# Main.net
KiCad netlist of a schematic drawn in Altium Designer
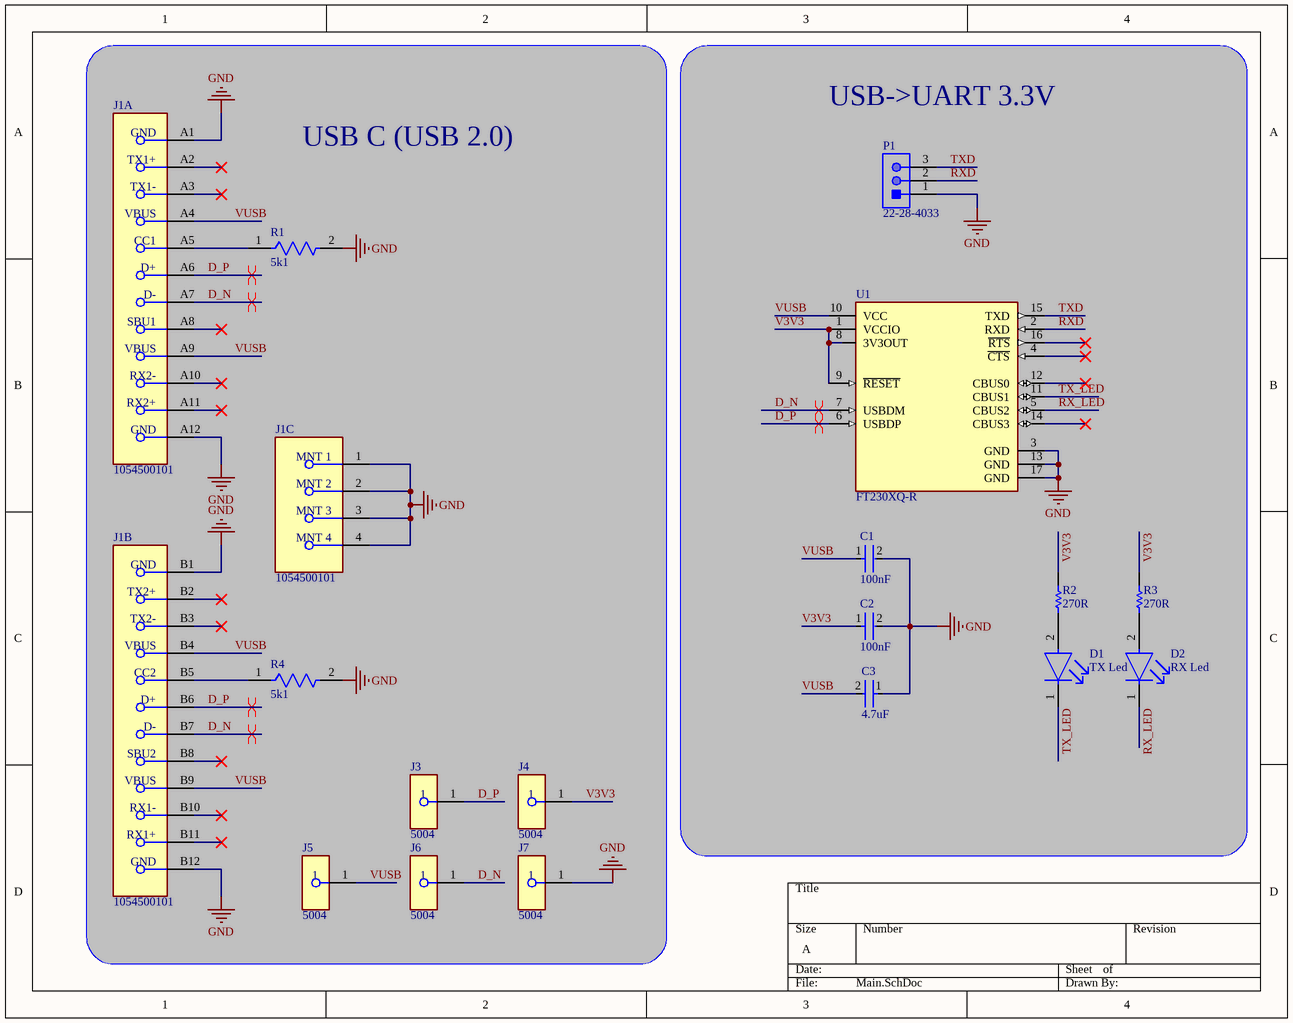
[diagram p0: Main.SchDoc]

(export (version "E")
  (design (tool "Eeschema 10.0.6"))
  (components
    (comp (ref "C1")
      (value "100nF")
      (footprint "FP-CGA3E-0_3-0_1-IPC_A")
      (description "Cap Ceramic 100nF 50V X7R 10% Pad SMD 0603 +125°C Automotive T/R")
      (fields (field (name "TOLERANCE") "10%") (field (name "VOLTAGE") "50V"))
      (libsource (lib "Altium Content Vault") (part "b4654b650e69147ec39a6b967a45e02"))
    )
    (comp (ref "C2")
      (value "100nF")
      (footprint "FP-CGA3E-0_3-0_1-IPC_A")
      (description "Cap Ceramic 100nF 50V X7R 10% Pad SMD 0603 +125°C Automotive T/R")
      (fields (field (name "TOLERANCE") "10%") (field (name "VOLTAGE") "50V"))
      (libsource (lib "Altium Content Vault") (part "b4654b650e69147ec39a6b967a45e02"))
    )
    (comp (ref "C3")
      (value "4.7uF")
      (footprint "FP-GRM188-0_2-IPC_C")
      (description "Chip Multilayer Ceramic Capacitors for General Purpose, 0603, 4.7uF, X5R, 15%, 10%, 35V")
      (fields (field (name "VOLTAGE") "35V") (field (name "TOLERANCE") "10%"))
      (libsource (lib "Altium Content Vault") (part "11868f565c42a9108669ba33697ecf6"))
    )
    (comp (ref "D1")
      (value "TX Led")
      (footprint "FP-LTST-C190GKT-MFG")
      (description "LED GREEN CLEAR CHIP SMD")
      (fields (field (name "VOLTAGE") "2V"))
      (libsource (lib "Altium Content Vault") (part "8706943c75ba83719d021d2fdc84c58"))
    )
    (comp (ref "D2")
      (value "RX Led")
      (footprint "FP-LTST-C190GKT-MFG")
      (description "LED GREEN CLEAR CHIP SMD")
      (fields (field (name "VOLTAGE") "2V"))
      (libsource (lib "Altium Content Vault") (part "8706943c75ba83719d021d2fdc84c58"))
    )
    (comp (ref "J1")
      (value "1054500101")
      (footprint "FP-1054500101-MFG")
      (description "USB Shielded I/O Receptacle; Type C; Right Angle; Surface Mount; Gold over Nickel")
      (fields (field (name "MANUFACTURER") "Molex"))
      (libsource (lib "Altium Content Vault") (part "9808b19ecaf079fb99eed69f0495cd0"))
    )
    (comp (ref "J3")
      (value "5004")
      (footprint "FP-5004-MFG")
      (description "PC TEST POINT MINIATURE YELLOW")
      (fields
        (field (name "MANUFACTURER") "Keystone")
        (field (name "OCTOPART") "https://octopart.com/5004-keystone-28591")
      )
      (libsource (lib "Altium Content Vault") (part "98815daf2f2c152b0c43f5ab9800df6"))
    )
    (comp (ref "J4")
      (value "5004")
      (footprint "FP-5004-MFG")
      (description "PC TEST POINT MINIATURE YELLOW")
      (fields
        (field (name "MANUFACTURER") "Keystone")
        (field (name "OCTOPART") "https://octopart.com/5004-keystone-28591")
      )
      (libsource (lib "Altium Content Vault") (part "98815daf2f2c152b0c43f5ab9800df6"))
    )
    (comp (ref "J5")
      (value "5004")
      (footprint "FP-5004-MFG")
      (description "PC TEST POINT MINIATURE YELLOW")
      (fields
        (field (name "MANUFACTURER") "Keystone")
        (field (name "OCTOPART") "https://octopart.com/5004-keystone-28591")
      )
      (libsource (lib "Altium Content Vault") (part "98815daf2f2c152b0c43f5ab9800df6"))
    )
    (comp (ref "J6")
      (value "5004")
      (footprint "FP-5004-MFG")
      (description "PC TEST POINT MINIATURE YELLOW")
      (fields
        (field (name "MANUFACTURER") "Keystone")
        (field (name "OCTOPART") "https://octopart.com/5004-keystone-28591")
      )
      (libsource (lib "Altium Content Vault") (part "98815daf2f2c152b0c43f5ab9800df6"))
    )
    (comp (ref "J7")
      (value "5004")
      (footprint "FP-5004-MFG")
      (description "PC TEST POINT MINIATURE YELLOW")
      (fields
        (field (name "MANUFACTURER") "Keystone")
        (field (name "OCTOPART") "https://octopart.com/5004-keystone-28591")
      )
      (libsource (lib "Altium Content Vault") (part "98815daf2f2c152b0c43f5ab9800df6"))
    )
    (comp (ref "P1")
      (value "22-28-4033")
      (footprint "MOLX-22-28-4033_V")
      (description "Male Header, Pitch 2.54 mm, 1 x 3 Position, Height 8.38 mm, Tail Length 3.18 mm, RoHS, Bulk")
      (fields (field (name "MANUFACTURER") "Molex"))
      (libsource (lib "Altium Content Vault") (part "CN-1P-M-R3"))
    )
    (comp (ref "R1")
      (value "5k1")
      (footprint "FP-CRCW0603-e3-IPC_C")
      (description "RES Thick Film, 5.1kΩ, 1%, 0.1W, 100ppm/°C, 0603")
      (fields (field (name "TOLERANCE") "1%"))
      (libsource (lib "Altium Content Vault") (part "1029c3af85768c4190bb7ad29bc67b5"))
    )
    (comp (ref "R2")
      (value "270R")
      (footprint "RESC1608X55X30LL15T15")
      (fields (field (name "MANUFACTURER") "Panasonic") (field (name "PART NUMBER") "ERJ3EKF2700V"))
      (libsource (lib "Altium Content Vault") (part "RES"))
    )
    (comp (ref "R3")
      (value "270R")
      (footprint "RESC1608X55X30LL15T15")
      (fields (field (name "MANUFACTURER") "Panasonic") (field (name "PART NUMBER") "ERJ3EKF2700V"))
      (libsource (lib "Altium Content Vault") (part "RES"))
    )
    (comp (ref "R4")
      (value "5k1")
      (footprint "FP-CRCW0603-e3-IPC_C")
      (description "RES Thick Film, 5.1kΩ, 1%, 0.1W, 100ppm/°C, 0603")
      (fields (field (name "TOLERANCE") "1%"))
      (libsource (lib "Altium Content Vault") (part "1029c3af85768c4190bb7ad29bc67b5"))
    )
    (comp (ref "U1")
      (value "FT230XQ-R")
      (footprint "FP-QFN-16-MFG")
      (description "IC USB SERIAL BASIC UART 16QFN")
      (libsource (lib "Altium Content Vault") (part "29d2eb9587eff32afae5da052de4085"))
    )
  )
  (nets
    (net (code "1") (name "/D_N") (class "Default")
      (node (ref "J1") (pin "A7") (pinfunction "D-_A7") (pintype "passive"))
      (node (ref "J1") (pin "B7") (pinfunction "D-_B7") (pintype "passive"))
      (node (ref "J6") (pin "1") (pinfunction "1_1") (pintype "passive"))
      (node (ref "U1") (pin "7") (pinfunction "USBDM_7") (pintype "input"))
    )
    (net (code "2") (name "/D_P") (class "Default")
      (node (ref "J1") (pin "A6") (pinfunction "D+_A6") (pintype "passive"))
      (node (ref "J1") (pin "B6") (pinfunction "D+_B6") (pintype "passive"))
      (node (ref "J3") (pin "1") (pinfunction "1_1") (pintype "passive"))
      (node (ref "U1") (pin "6") (pinfunction "USBDP_6") (pintype "input"))
    )
    (net (code "3") (name "/RXD") (class "Default")
      (node (ref "P1") (pin "2") (pinfunction "2_2") (pintype "passive"))
      (node (ref "U1") (pin "2") (pinfunction "RXD_2") (pintype "input"))
    )
    (net (code "4") (name "/RX_LED") (class "Default")
      (node (ref "D2") (pin "1") (pinfunction "C_1") (pintype "passive"))
      (node (ref "U1") (pin "5") (pinfunction "CBUS2_5") (pintype "bidirectional"))
    )
    (net (code "5") (name "/TXD") (class "Default")
      (node (ref "P1") (pin "3") (pinfunction "3_3") (pintype "passive"))
      (node (ref "U1") (pin "15") (pinfunction "TXD_15") (pintype "output"))
    )
    (net (code "6") (name "/TX_LED") (class "Default")
      (node (ref "D1") (pin "1") (pinfunction "C_1") (pintype "passive"))
      (node (ref "U1") (pin "11") (pinfunction "CBUS1_11") (pintype "bidirectional"))
    )
    (net (code "7") (name "/V3V3") (class "Default")
      (node (ref "C2") (pin "1") (pinfunction "1_1") (pintype "passive"))
      (node (ref "J4") (pin "1") (pinfunction "1_1") (pintype "passive"))
      (node (ref "R2") (pin "2") (pinfunction "2_2") (pintype "passive"))
      (node (ref "R3") (pin "2") (pinfunction "2_2") (pintype "passive"))
      (node (ref "U1") (pin "1") (pinfunction "VCCIO_1") (pintype "power_in"))
      (node (ref "U1") (pin "8") (pinfunction "3V3OUT_8") (pintype "power_in"))
      (node (ref "U1") (pin "9") (pinfunction "~{RESET}_9") (pintype "input"))
    )
    (net (code "8") (name "/VUSB") (class "Default")
      (node (ref "C1") (pin "1") (pinfunction "1_1") (pintype "passive"))
      (node (ref "C3") (pin "2") (pinfunction "2_2") (pintype "passive"))
      (node (ref "J1") (pin "A4") (pinfunction "VBUS_A4") (pintype "passive"))
      (node (ref "J1") (pin "A9") (pinfunction "VBUS_A9") (pintype "passive"))
      (node (ref "J1") (pin "B4") (pinfunction "VBUS_B4") (pintype "passive"))
      (node (ref "J1") (pin "B9") (pinfunction "VBUS_B9") (pintype "passive"))
      (node (ref "J5") (pin "1") (pinfunction "1_1") (pintype "passive"))
      (node (ref "U1") (pin "10") (pinfunction "VCC_10") (pintype "power_in"))
    )
    (net (code "9") (name "GND") (class "Default")
      (node (ref "C1") (pin "2") (pinfunction "2_2") (pintype "passive"))
      (node (ref "C2") (pin "2") (pinfunction "2_2") (pintype "passive"))
      (node (ref "C3") (pin "1") (pinfunction "1_1") (pintype "passive"))
      (node (ref "J1") (pin "1") (pinfunction "MNT_1_1") (pintype "passive"))
      (node (ref "J1") (pin "2") (pinfunction "MNT_2_2") (pintype "passive"))
      (node (ref "J1") (pin "3") (pinfunction "MNT_3_3") (pintype "passive"))
      (node (ref "J1") (pin "4") (pinfunction "MNT_4_4") (pintype "passive"))
      (node (ref "J1") (pin "A1") (pinfunction "GND_A1") (pintype "passive"))
      (node (ref "J1") (pin "A12") (pinfunction "GND_A12") (pintype "passive"))
      (node (ref "J1") (pin "B1") (pinfunction "GND_B1") (pintype "passive"))
      (node (ref "J1") (pin "B12") (pinfunction "GND_B12") (pintype "passive"))
      (node (ref "J7") (pin "1") (pinfunction "1_1") (pintype "passive"))
      (node (ref "P1") (pin "1") (pinfunction "1_1") (pintype "passive"))
      (node (ref "R1") (pin "2") (pinfunction "2_2") (pintype "passive"))
      (node (ref "R4") (pin "2") (pinfunction "2_2") (pintype "passive"))
      (node (ref "U1") (pin "13") (pinfunction "GND_13") (pintype "power_in"))
      (node (ref "U1") (pin "17") (pinfunction "GND_17") (pintype "power_in"))
      (node (ref "U1") (pin "3") (pinfunction "GND_3") (pintype "power_in"))
    )
    (net (code "10") (name "Net-(D1-A)") (class "Default")
      (node (ref "D1") (pin "2") (pinfunction "A_2") (pintype "passive"))
      (node (ref "R2") (pin "1") (pinfunction "1_1") (pintype "passive"))
    )
    (net (code "11") (name "Net-(D2-A)") (class "Default")
      (node (ref "D2") (pin "2") (pinfunction "A_2") (pintype "passive"))
      (node (ref "R3") (pin "1") (pinfunction "1_1") (pintype "passive"))
    )
    (net (code "12") (name "Net-(J1A-CC1)") (class "Default")
      (node (ref "J1") (pin "A5") (pinfunction "CC1_A5") (pintype "passive"))
      (node (ref "R1") (pin "1") (pinfunction "1_1") (pintype "passive"))
    )
    (net (code "13") (name "Net-(J1B-CC2)") (class "Default")
      (node (ref "J1") (pin "B5") (pinfunction "CC2_B5") (pintype "passive"))
      (node (ref "R4") (pin "1") (pinfunction "1_1") (pintype "passive"))
    )
    (net (code "14") (name "unconnected-(J1A-RX2+-PadA11)") (class "Default")
      (node (ref "J1") (pin "A11") (pinfunction "RX2+_A11") (pintype "passive+no_connect"))
    )
    (net (code "15") (name "unconnected-(J1A-RX2--PadA10)") (class "Default")
      (node (ref "J1") (pin "A10") (pinfunction "RX2-_A10") (pintype "passive+no_connect"))
    )
    (net (code "16") (name "unconnected-(J1A-SBU1-PadA8)") (class "Default")
      (node (ref "J1") (pin "A8") (pinfunction "SBU1_A8") (pintype "passive+no_connect"))
    )
    (net (code "17") (name "unconnected-(J1A-TX1+-PadA2)") (class "Default")
      (node (ref "J1") (pin "A2") (pinfunction "TX1+_A2") (pintype "passive+no_connect"))
    )
    (net (code "18") (name "unconnected-(J1A-TX1--PadA3)") (class "Default")
      (node (ref "J1") (pin "A3") (pinfunction "TX1-_A3") (pintype "passive+no_connect"))
    )
    (net (code "19") (name "unconnected-(J1B-RX1+-PadB11)") (class "Default")
      (node (ref "J1") (pin "B11") (pinfunction "RX1+_B11") (pintype "passive+no_connect"))
    )
    (net (code "20") (name "unconnected-(J1B-RX1--PadB10)") (class "Default")
      (node (ref "J1") (pin "B10") (pinfunction "RX1-_B10") (pintype "passive+no_connect"))
    )
    (net (code "21") (name "unconnected-(J1B-SBU2-PadB8)") (class "Default")
      (node (ref "J1") (pin "B8") (pinfunction "SBU2_B8") (pintype "passive+no_connect"))
    )
    (net (code "22") (name "unconnected-(J1B-TX2+-PadB2)") (class "Default")
      (node (ref "J1") (pin "B2") (pinfunction "TX2+_B2") (pintype "passive+no_connect"))
    )
    (net (code "23") (name "unconnected-(J1B-TX2--PadB3)") (class "Default")
      (node (ref "J1") (pin "B3") (pinfunction "TX2-_B3") (pintype "passive+no_connect"))
    )
    (net (code "24") (name "unconnected-(U1-CBUS0-Pad12)") (class "Default")
      (node (ref "U1") (pin "12") (pinfunction "CBUS0_12") (pintype "bidirectional+no_connect"))
    )
    (net (code "25") (name "unconnected-(U1-CBUS3-Pad14)") (class "Default")
      (node (ref "U1") (pin "14") (pinfunction "CBUS3_14") (pintype "bidirectional+no_connect"))
    )
    (net (code "26") (name "unconnected-(U1-~{CTS}-Pad4)") (class "Default")
      (node (ref "U1") (pin "4") (pinfunction "~{CTS}_4") (pintype "input+no_connect"))
    )
    (net (code "27") (name "unconnected-(U1-~{RTS}-Pad16)") (class "Default")
      (node (ref "U1") (pin "16") (pinfunction "~{RTS}_16") (pintype "output+no_connect"))
    )
  )
)
